# Interface.net
KiCad netlist of a schematic drawn in Altium Designer
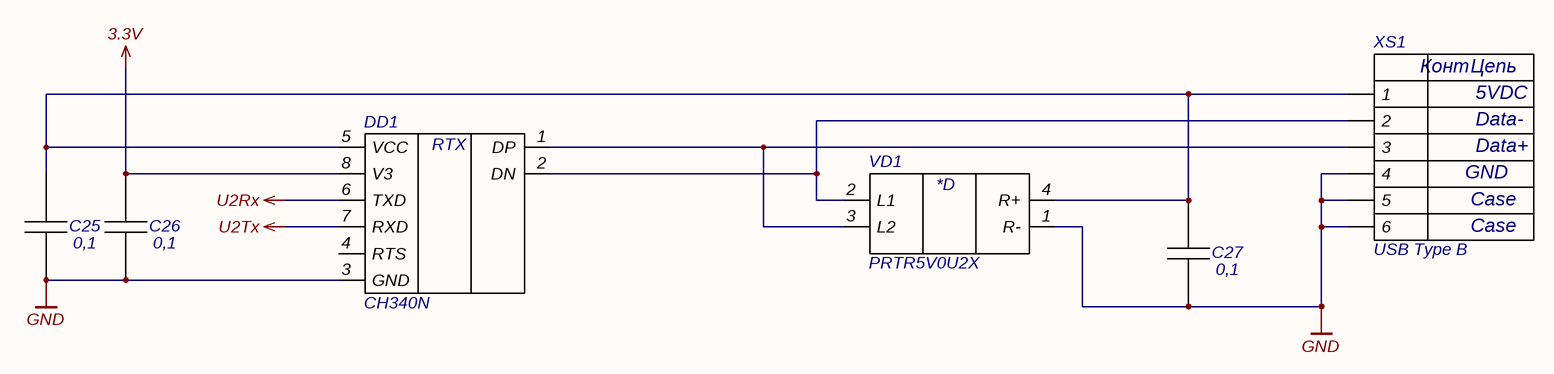
[diagram p0: Interface.SchDoc]

(export (version "E")
  (design (tool "Eeschema 10.0.6"))
  (components
    (comp (ref "C25")
      (value "0,1")
      (footprint "C0603")
      (description "Чип-конденсатор")
      (libsource (lib "Passive") (part "Chip Capasitor"))
    )
    (comp (ref "C26")
      (value "0,1")
      (footprint "C0603")
      (description "Чип-конденсатор")
      (libsource (lib "Passive") (part "Chip Capasitor"))
    )
    (comp (ref "C27")
      (value "0,1")
      (footprint "C0603")
      (description "Чип-конденсатор")
      (libsource (lib "Passive") (part "Chip Capasitor"))
    )
    (comp (ref "DD1")
      (value "CH340N")
      (footprint "SOP-8 (SOIC)")
      (description "Преобразователь интерфейса USB в UART")
      (fields (field (name "MANUFACTURER") "Nanjing Qinheng Microelectronics"))
      (libsource (lib "Schlib") (part "CH340N"))
    )
    (comp (ref "VD1")
      (value "PRTR5V0U2X")
      (footprint "SOT-143")
      (description "Защитная диодная сборка от статического заряда")
      (fields (field (name "MANUFACTURER") "UTD Semiconductor (UMW)"))
      (libsource (lib "Schlib") (part "PRTR5V0U2X"))
    )
    (comp (ref "XS1")
      (value "USB Type B")
      (footprint "USB Type B")
      (description "Гнездо USB тип B")
      (fields (field (name "MANUFACTURER") "Connfly electronic (Zhenqin)"))
      (libsource (lib "Schlib") (part "USB Type B"))
    )
  )
  (nets
    (net (code "1") (name "3.3V") (class "Default")
      (node (ref "C26") (pin "2") (pinfunction "2_2") (pintype "passive"))
      (node (ref "DD1") (pin "8") (pinfunction "V3_8") (pintype "passive"))
    )
    (net (code "2") (name "GND") (class "Default")
      (node (ref "C25") (pin "1") (pinfunction "1_1") (pintype "passive"))
      (node (ref "C26") (pin "1") (pinfunction "1_1") (pintype "passive"))
      (node (ref "C27") (pin "1") (pinfunction "1_1") (pintype "passive"))
      (node (ref "DD1") (pin "3") (pinfunction "GND_3") (pintype "passive"))
      (node (ref "VD1") (pin "1") (pinfunction "R-_1") (pintype "passive"))
      (node (ref "XS1") (pin "4") (pinfunction "4_4") (pintype "passive"))
      (node (ref "XS1") (pin "5") (pinfunction "5_5") (pintype "passive"))
      (node (ref "XS1") (pin "6") (pinfunction "6_6") (pintype "passive"))
    )
    (net (code "3") (name "Net-(DD1-DN)") (class "Default")
      (node (ref "DD1") (pin "2") (pinfunction "DN_2") (pintype "passive"))
      (node (ref "VD1") (pin "2") (pinfunction "L1_2") (pintype "passive"))
      (node (ref "XS1") (pin "2") (pinfunction "2_2") (pintype "passive"))
    )
    (net (code "4") (name "Net-(DD1-DP)") (class "Default")
      (node (ref "DD1") (pin "1") (pinfunction "DP_1") (pintype "passive"))
      (node (ref "VD1") (pin "3") (pinfunction "L2_3") (pintype "passive"))
      (node (ref "XS1") (pin "3") (pinfunction "3_3") (pintype "passive"))
    )
    (net (code "5") (name "Net-(DD1-VCC)") (class "Default")
      (node (ref "C25") (pin "2") (pinfunction "2_2") (pintype "passive"))
      (node (ref "C27") (pin "2") (pinfunction "2_2") (pintype "passive"))
      (node (ref "DD1") (pin "5") (pinfunction "VCC_5") (pintype "passive"))
      (node (ref "VD1") (pin "4") (pinfunction "R+_4") (pintype "passive"))
      (node (ref "XS1") (pin "1") (pinfunction "1_1") (pintype "passive"))
    )
    (net (code "6") (name "U2Rx") (class "Default")
      (node (ref "DD1") (pin "6") (pinfunction "TXD_6") (pintype "passive"))
    )
    (net (code "7") (name "U2Tx") (class "Default")
      (node (ref "DD1") (pin "7") (pinfunction "RXD_7") (pintype "passive"))
    )
    (net (code "8") (name "unconnected-(DD1-RTS-Pad4)") (class "Default")
      (node (ref "DD1") (pin "4") (pinfunction "RTS_4") (pintype "passive"))
    )
  )
)
